# star.net
KiCad netlist of a schematic drawn in EAGLE
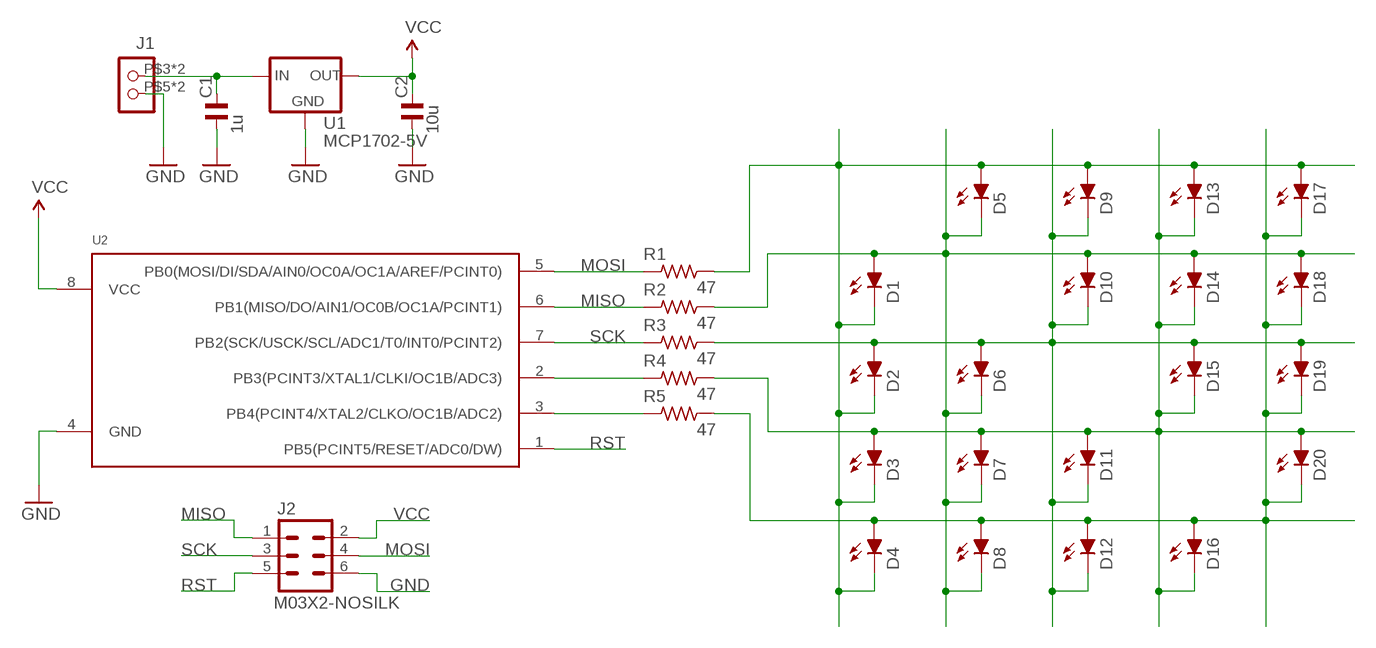
[diagram p0: schematic, sheet 1]

(export (version "E")
  (design (tool "Eeschema 10.0.6"))
  (components
    (comp (ref "C1")
      (value "1u")
      (footprint "eagle-import:C0805NOSILK")
      (libsource (lib "eagle-import") (part "C_0805NOSILK"))
    )
    (comp (ref "C2")
      (value "10u")
      (footprint "eagle-import:C0805NOSILK")
      (libsource (lib "eagle-import") (part "C_0805NOSILK"))
    )
    (comp (ref "D1")
      (value "LEDCHIP-LED0805NOSILK")
      (footprint "eagle-import:CHIP-LED0805NOSILK")
      (libsource (lib "eagle-import") (part "LEDCHIP-LED0805NOSILK"))
    )
    (comp (ref "D2")
      (value "LEDCHIP-LED0805NOSILK")
      (footprint "eagle-import:CHIP-LED0805NOSILK")
      (libsource (lib "eagle-import") (part "LEDCHIP-LED0805NOSILK"))
    )
    (comp (ref "D3")
      (value "LEDCHIP-LED0805NOSILK")
      (footprint "eagle-import:CHIP-LED0805NOSILK")
      (libsource (lib "eagle-import") (part "LEDCHIP-LED0805NOSILK"))
    )
    (comp (ref "D4")
      (value "LEDCHIP-LED0805NOSILK")
      (footprint "eagle-import:CHIP-LED0805NOSILK")
      (libsource (lib "eagle-import") (part "LEDCHIP-LED0805NOSILK"))
    )
    (comp (ref "D5")
      (value "LEDCHIP-LED0805NOSILK")
      (footprint "eagle-import:CHIP-LED0805NOSILK")
      (libsource (lib "eagle-import") (part "LEDCHIP-LED0805NOSILK"))
    )
    (comp (ref "D6")
      (value "LEDCHIP-LED0805NOSILK")
      (footprint "eagle-import:CHIP-LED0805NOSILK")
      (libsource (lib "eagle-import") (part "LEDCHIP-LED0805NOSILK"))
    )
    (comp (ref "D7")
      (value "LEDCHIP-LED0805NOSILK")
      (footprint "eagle-import:CHIP-LED0805NOSILK")
      (libsource (lib "eagle-import") (part "LEDCHIP-LED0805NOSILK"))
    )
    (comp (ref "D8")
      (value "LEDCHIP-LED0805NOSILK")
      (footprint "eagle-import:CHIP-LED0805NOSILK")
      (libsource (lib "eagle-import") (part "LEDCHIP-LED0805NOSILK"))
    )
    (comp (ref "D9")
      (value "LEDCHIP-LED0805NOSILK")
      (footprint "eagle-import:CHIP-LED0805NOSILK")
      (libsource (lib "eagle-import") (part "LEDCHIP-LED0805NOSILK"))
    )
    (comp (ref "D10")
      (value "LEDCHIP-LED0805NOSILK")
      (footprint "eagle-import:CHIP-LED0805NOSILK")
      (libsource (lib "eagle-import") (part "LEDCHIP-LED0805NOSILK"))
    )
    (comp (ref "D11")
      (value "LEDCHIP-LED0805NOSILK")
      (footprint "eagle-import:CHIP-LED0805NOSILK")
      (libsource (lib "eagle-import") (part "LEDCHIP-LED0805NOSILK"))
    )
    (comp (ref "D12")
      (value "LEDCHIP-LED0805NOSILK")
      (footprint "eagle-import:CHIP-LED0805NOSILK")
      (libsource (lib "eagle-import") (part "LEDCHIP-LED0805NOSILK"))
    )
    (comp (ref "D13")
      (value "LEDCHIP-LED0805NOSILK")
      (footprint "eagle-import:CHIP-LED0805NOSILK")
      (libsource (lib "eagle-import") (part "LEDCHIP-LED0805NOSILK"))
    )
    (comp (ref "D14")
      (value "LEDCHIP-LED0805NOSILK")
      (footprint "eagle-import:CHIP-LED0805NOSILK")
      (libsource (lib "eagle-import") (part "LEDCHIP-LED0805NOSILK"))
    )
    (comp (ref "D15")
      (value "LEDCHIP-LED0805NOSILK")
      (footprint "eagle-import:CHIP-LED0805NOSILK")
      (libsource (lib "eagle-import") (part "LEDCHIP-LED0805NOSILK"))
    )
    (comp (ref "D16")
      (value "LEDCHIP-LED0805NOSILK")
      (footprint "eagle-import:CHIP-LED0805NOSILK")
      (libsource (lib "eagle-import") (part "LEDCHIP-LED0805NOSILK"))
    )
    (comp (ref "D17")
      (value "LEDCHIP-LED0805NOSILK")
      (footprint "eagle-import:CHIP-LED0805NOSILK")
      (libsource (lib "eagle-import") (part "LEDCHIP-LED0805NOSILK"))
    )
    (comp (ref "D18")
      (value "LEDCHIP-LED0805NOSILK")
      (footprint "eagle-import:CHIP-LED0805NOSILK")
      (libsource (lib "eagle-import") (part "LEDCHIP-LED0805NOSILK"))
    )
    (comp (ref "D19")
      (value "LEDCHIP-LED0805NOSILK")
      (footprint "eagle-import:CHIP-LED0805NOSILK")
      (libsource (lib "eagle-import") (part "LEDCHIP-LED0805NOSILK"))
    )
    (comp (ref "D20")
      (value "LEDCHIP-LED0805NOSILK")
      (footprint "eagle-import:CHIP-LED0805NOSILK")
      (libsource (lib "eagle-import") (part "LEDCHIP-LED0805NOSILK"))
    )
    (comp (ref "J1")
      (value "CON_TERMINAL_HOLES")
      (footprint "eagle-import:TERMINAL_2P_4H")
      (libsource (lib "eagle-import") (part "CON_TERMINAL_HOLES"))
    )
    (comp (ref "J2")
      (value "M03X2-NOSILK")
      (footprint "eagle-import:2X03_LOCK_NOSILK")
      (libsource (lib "eagle-import") (part "M03X2-NOSILK"))
    )
    (comp (ref "R1")
      (value "47")
      (footprint "eagle-import:R0805NOSILK")
      (libsource (lib "eagle-import") (part "R_0805NOSILK"))
    )
    (comp (ref "R2")
      (value "47")
      (footprint "eagle-import:R0805NOSILK")
      (libsource (lib "eagle-import") (part "R_0805NOSILK"))
    )
    (comp (ref "R3")
      (value "47")
      (footprint "eagle-import:R0805NOSILK")
      (libsource (lib "eagle-import") (part "R_0805NOSILK"))
    )
    (comp (ref "R4")
      (value "47")
      (footprint "eagle-import:R0805NOSILK")
      (libsource (lib "eagle-import") (part "R_0805NOSILK"))
    )
    (comp (ref "R5")
      (value "47")
      (footprint "eagle-import:R0805NOSILK")
      (libsource (lib "eagle-import") (part "R_0805NOSILK"))
    )
    (comp (ref "U1")
      (value "MCP1702-5V")
      (footprint "eagle-import:SOT23_NOSILK")
      (libsource (lib "eagle-import") (part "V_REG_MCP170X-CB-NOSILK"))
    )
    (comp (ref "U2")
      (value "ATTINY5-20SU-NOSILK")
      (footprint "eagle-import:SOP8-8S2-NOSILK")
      (libsource (lib "eagle-import") (part "ATTINY5-20SU-NOSILK"))
    )
  )
  (nets
    (net (code "1") (name "/MISO") (class "Default")
      (node (ref "J2") (pin "1") (pinfunction "1_1") (pintype "passive"))
      (node (ref "R2") (pin "1") (pinfunction "1_1") (pintype "passive"))
      (node (ref "U2") (pin "6") (pinfunction "PB1(MISO/DO/AIN1/OC0B/OC1A/PCINT1)_6") (pintype "bidirectional"))
    )
    (net (code "2") (name "/MOSI") (class "Default")
      (node (ref "J2") (pin "4") (pinfunction "4_4") (pintype "passive"))
      (node (ref "R1") (pin "1") (pinfunction "1_1") (pintype "passive"))
      (node (ref "U2") (pin "5") (pinfunction "PB0(MOSI/DI/SDA/AIN0/OC0A/OC1A/AREF/PCINT0)_5") (pintype "bidirectional"))
    )
    (net (code "3") (name "/RST") (class "Default")
      (node (ref "J2") (pin "5") (pinfunction "5_5") (pintype "passive"))
      (node (ref "U2") (pin "1") (pinfunction "PB5(PCINT5/RESET/ADC0/DW)_1") (pintype "bidirectional"))
    )
    (net (code "4") (name "/SCK") (class "Default")
      (node (ref "J2") (pin "3") (pinfunction "3_3") (pintype "passive"))
      (node (ref "R3") (pin "1") (pinfunction "1_1") (pintype "passive"))
      (node (ref "U2") (pin "7") (pinfunction "PB2(SCK/USCK/SCL/ADC1/T0/INT0/PCINT2)_7") (pintype "bidirectional"))
    )
    (net (code "5") (name "GND") (class "Default")
      (node (ref "C1") (pin "1") (pinfunction "1_1") (pintype "passive"))
      (node (ref "C2") (pin "1") (pinfunction "1_1") (pintype "passive"))
      (node (ref "J1") (pin "P$5") (pinfunction "2_P$5") (pintype "passive"))
      (node (ref "J1") (pin "P$6") (pinfunction "2_P$6") (pintype "passive"))
      (node (ref "J2") (pin "6") (pinfunction "6_6") (pintype "passive"))
      (node (ref "U1") (pin "1") (pinfunction "GND_1") (pintype "input"))
      (node (ref "U2") (pin "4") (pinfunction "GND_4") (pintype "bidirectional"))
    )
    (net (code "6") (name "Net-(D1-PadA)") (class "Default")
      (node (ref "D1") (pin "A") (pinfunction "A_A") (pintype "passive"))
      (node (ref "D10") (pin "A") (pinfunction "A_A") (pintype "passive"))
      (node (ref "D14") (pin "A") (pinfunction "A_A") (pintype "passive"))
      (node (ref "D18") (pin "A") (pinfunction "A_A") (pintype "passive"))
      (node (ref "D5") (pin "C") (pinfunction "C_C") (pintype "passive"))
      (node (ref "D6") (pin "C") (pinfunction "C_C") (pintype "passive"))
      (node (ref "D7") (pin "C") (pinfunction "C_C") (pintype "passive"))
      (node (ref "D8") (pin "C") (pinfunction "C_C") (pintype "passive"))
      (node (ref "R2") (pin "2") (pinfunction "2_2") (pintype "passive"))
    )
    (net (code "7") (name "Net-(D1-PadC)") (class "Default")
      (node (ref "D1") (pin "C") (pinfunction "C_C") (pintype "passive"))
      (node (ref "D13") (pin "A") (pinfunction "A_A") (pintype "passive"))
      (node (ref "D17") (pin "A") (pinfunction "A_A") (pintype "passive"))
      (node (ref "D2") (pin "C") (pinfunction "C_C") (pintype "passive"))
      (node (ref "D3") (pin "C") (pinfunction "C_C") (pintype "passive"))
      (node (ref "D4") (pin "C") (pinfunction "C_C") (pintype "passive"))
      (node (ref "D5") (pin "A") (pinfunction "A_A") (pintype "passive"))
      (node (ref "D9") (pin "A") (pinfunction "A_A") (pintype "passive"))
      (node (ref "R1") (pin "2") (pinfunction "2_2") (pintype "passive"))
    )
    (net (code "8") (name "Net-(D10-PadC)") (class "Default")
      (node (ref "D10") (pin "C") (pinfunction "C_C") (pintype "passive"))
      (node (ref "D11") (pin "C") (pinfunction "C_C") (pintype "passive"))
      (node (ref "D12") (pin "C") (pinfunction "C_C") (pintype "passive"))
      (node (ref "D15") (pin "A") (pinfunction "A_A") (pintype "passive"))
      (node (ref "D19") (pin "A") (pinfunction "A_A") (pintype "passive"))
      (node (ref "D2") (pin "A") (pinfunction "A_A") (pintype "passive"))
      (node (ref "D6") (pin "A") (pinfunction "A_A") (pintype "passive"))
      (node (ref "D9") (pin "C") (pinfunction "C_C") (pintype "passive"))
      (node (ref "R3") (pin "2") (pinfunction "2_2") (pintype "passive"))
    )
    (net (code "9") (name "Net-(D11-PadA)") (class "Default")
      (node (ref "D11") (pin "A") (pinfunction "A_A") (pintype "passive"))
      (node (ref "D13") (pin "C") (pinfunction "C_C") (pintype "passive"))
      (node (ref "D14") (pin "C") (pinfunction "C_C") (pintype "passive"))
      (node (ref "D15") (pin "C") (pinfunction "C_C") (pintype "passive"))
      (node (ref "D16") (pin "C") (pinfunction "C_C") (pintype "passive"))
      (node (ref "D20") (pin "A") (pinfunction "A_A") (pintype "passive"))
      (node (ref "D3") (pin "A") (pinfunction "A_A") (pintype "passive"))
      (node (ref "D7") (pin "A") (pinfunction "A_A") (pintype "passive"))
      (node (ref "R4") (pin "2") (pinfunction "2_2") (pintype "passive"))
    )
    (net (code "10") (name "Net-(D12-PadA)") (class "Default")
      (node (ref "D12") (pin "A") (pinfunction "A_A") (pintype "passive"))
      (node (ref "D16") (pin "A") (pinfunction "A_A") (pintype "passive"))
      (node (ref "D17") (pin "C") (pinfunction "C_C") (pintype "passive"))
      (node (ref "D18") (pin "C") (pinfunction "C_C") (pintype "passive"))
      (node (ref "D19") (pin "C") (pinfunction "C_C") (pintype "passive"))
      (node (ref "D20") (pin "C") (pinfunction "C_C") (pintype "passive"))
      (node (ref "D4") (pin "A") (pinfunction "A_A") (pintype "passive"))
      (node (ref "D8") (pin "A") (pinfunction "A_A") (pintype "passive"))
      (node (ref "R5") (pin "2") (pinfunction "2_2") (pintype "passive"))
    )
    (net (code "11") (name "Net-(U1-IN)") (class "Default")
      (node (ref "C1") (pin "2") (pinfunction "2_2") (pintype "passive"))
      (node (ref "J1") (pin "P$3") (pinfunction "1_P$3") (pintype "passive"))
      (node (ref "J1") (pin "P$4") (pinfunction "1_P$4") (pintype "passive"))
      (node (ref "U1") (pin "3") (pinfunction "IN_3") (pintype "input"))
    )
    (net (code "12") (name "Net-(U2-PB3(PCINT3{slash}XTAL1{slash}CLKI{slash}OC1B{slash}ADC3))") (class "Default")
      (node (ref "R4") (pin "1") (pinfunction "1_1") (pintype "passive"))
      (node (ref "U2") (pin "2") (pinfunction "PB3(PCINT3/XTAL1/CLKI/OC1B/ADC3)_2") (pintype "bidirectional"))
    )
    (net (code "13") (name "Net-(U2-PB4(PCINT4{slash}XTAL2{slash}CLKO{slash}OC1B{slash}ADC2))") (class "Default")
      (node (ref "R5") (pin "1") (pinfunction "1_1") (pintype "passive"))
      (node (ref "U2") (pin "3") (pinfunction "PB4(PCINT4/XTAL2/CLKO/OC1B/ADC2)_3") (pintype "bidirectional"))
    )
    (net (code "14") (name "VCC") (class "Default")
      (node (ref "C2") (pin "2") (pinfunction "2_2") (pintype "passive"))
      (node (ref "J2") (pin "2") (pinfunction "2_2") (pintype "passive"))
      (node (ref "U1") (pin "2") (pinfunction "OUT_2") (pintype "power_in"))
      (node (ref "U2") (pin "8") (pinfunction "VCC_8") (pintype "bidirectional"))
    )
  )
)
